# hv_io_connector.net
KiCad netlist of a schematic drawn in Altium Designer
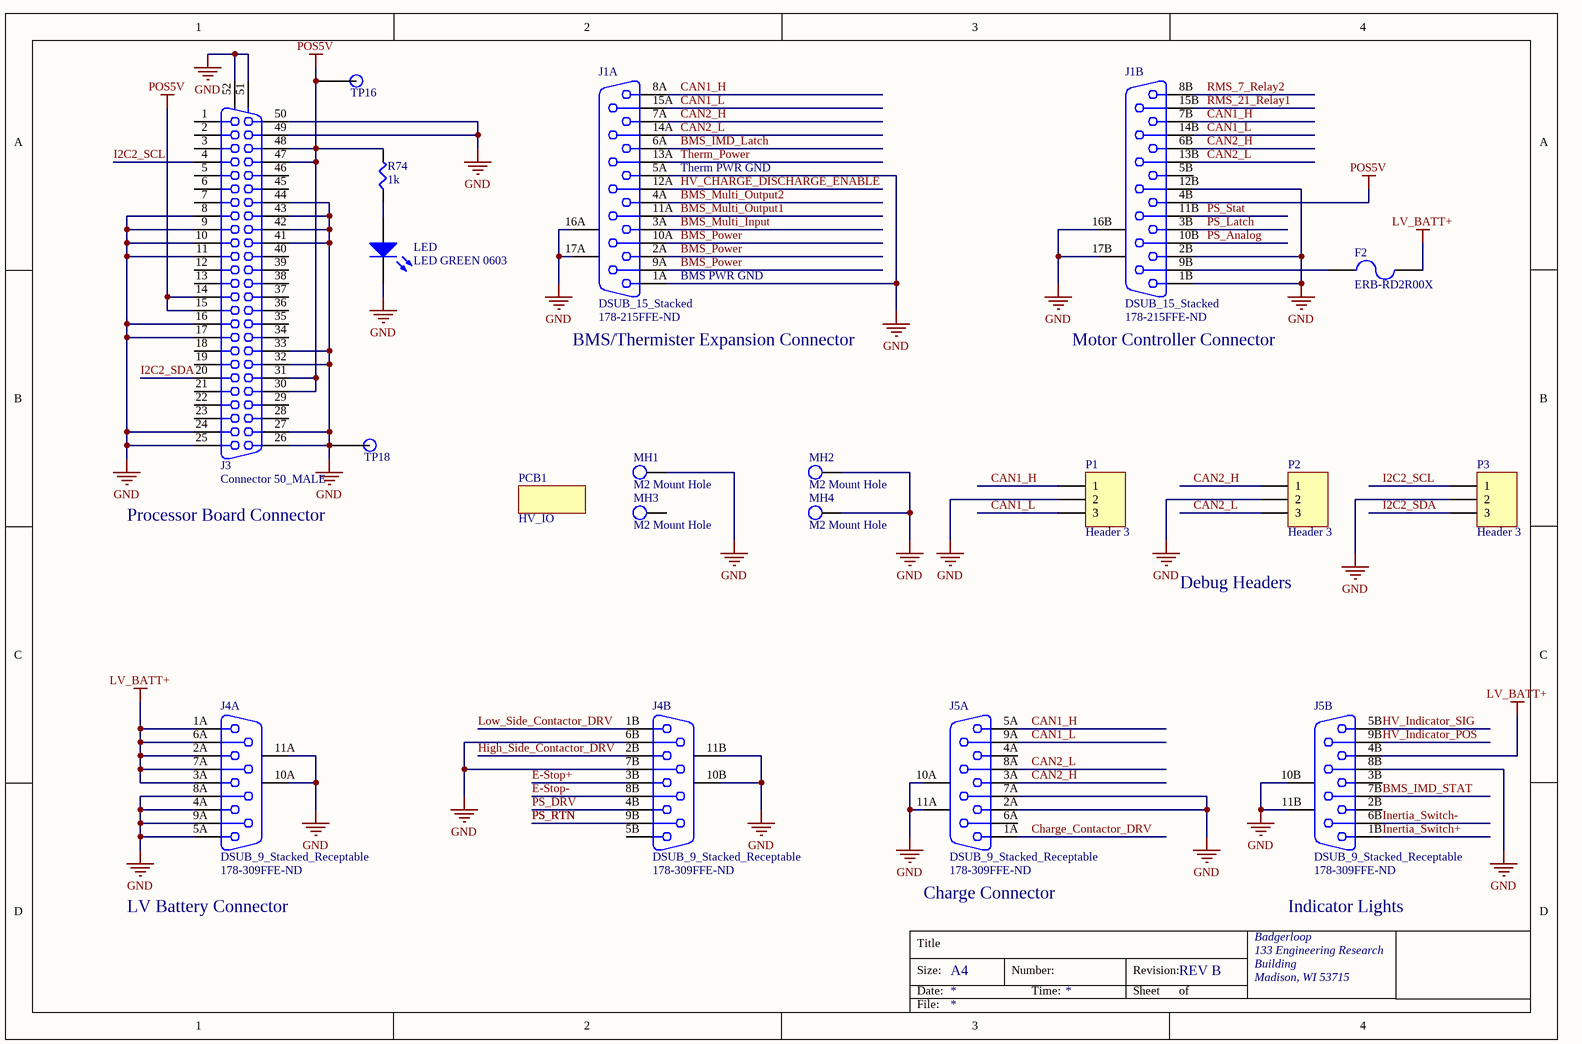
[diagram p0: hv_io_connector.SchDoc]

(export (version "E")
  (design (tool "Eeschema 10.0.6"))
  (components
    (comp (ref "F2")
      (value "ERB-RD2R00X")
      (footprint "SMD-0402-RES")
      (description "FUSE BOARD MOUNT 2A 32VDC 0402")
      (fields (field (name "MANUFACTURER") "Panasonic"))
      (libsource (lib "temp") (part "ERB-RD2R00X"))
    )
    (comp (ref "J1")
      (value "DSUB_15_Stacked")
      (footprint "DSUB_15_Stacked")
      (description "CONN D-SUB RCPT 15POS R/A SLDR")
      (fields
        (field (name "MANUFACTURER") "NorComp")
        (field (name "MANUFACTURER PART NUMBER") "178-015-513R491")
        (field (name "SUPPLIER PART NUMBER 1") "178-215FFE-ND")
      )
      (libsource (lib "temp") (part "DSUB_15_Stacked"))
    )
    (comp (ref "J3")
      (value "Connector 50_MALE")
      (footprint "050DSUB1.27-H96 - Male")
      (description "Receptacle Header Assemby")
      (fields (field (name "MANUFACTURER") "HARTING"))
      (libsource (lib "connector") (part "Connector 50_MALE"))
    )
    (comp (ref "J4")
      (value "DSUB_9_Stacked_Receptable")
      (footprint "DSUB_9_Stacked")
      (description "CONN D-SUB RCPT 9POS R/A SLDR")
      (fields
        (field (name "MANUFACTURER") "NorComp")
        (field (name "MANUFACTURER PART NUMBER") "178-009-513R691")
        (field (name "SUPPLIER PART NUMBER 1") "178-309FFE-ND")
      )
      (libsource (lib "temp") (part "DSUB_9_Stacked_Receptable"))
    )
    (comp (ref "J5")
      (value "DSUB_9_Stacked_Receptable")
      (footprint "DSUB_9_Stacked")
      (description "CONN D-SUB RCPT 9POS R/A SLDR")
      (fields
        (field (name "MANUFACTURER") "NorComp")
        (field (name "MANUFACTURER PART NUMBER") "178-009-513R691")
        (field (name "SUPPLIER PART NUMBER 1") "178-309FFE-ND")
      )
      (libsource (lib "temp") (part "DSUB_9_Stacked_Receptable"))
    )
    (comp (ref "LED")
      (value "LED GREEN 0603")
      (footprint "LED 0603 GREEN")
      (fields (field (name "MANUFACTURER") "Lite-On Inc."))
      (libsource (lib "altium-import") (part "root_3_LED GREEN 0603_"))
    )
    (comp (ref "MH1")
      (value "M2 Mount Hole")
      (footprint "MH")
      (libsource (lib "altium-import") (part "root_0_M2 Mount Hole_"))
    )
    (comp (ref "MH2")
      (value "M2 Mount Hole")
      (footprint "MH")
      (libsource (lib "altium-import") (part "root_0_M2 Mount Hole_"))
    )
    (comp (ref "MH3")
      (value "M2 Mount Hole")
      (footprint "MH")
      (libsource (lib "altium-import") (part "root_0_M2 Mount Hole_"))
    )
    (comp (ref "MH4")
      (value "M2 Mount Hole")
      (footprint "MH")
      (libsource (lib "altium-import") (part "root_0_M2 Mount Hole_"))
    )
    (comp (ref "P1")
      (value "Header 3")
      (footprint "Pin Header 1x3 TH Pitch 2.54mm")
      (description "Header, 3-Pin")
      (fields (field (name "PUBLISHER") "Altium Limited"))
      (libsource (lib "altium-import") (part "root_0_Header 3_"))
    )
    (comp (ref "P2")
      (value "Header 3")
      (footprint "Pin Header 1x3 TH Pitch 2.54mm")
      (description "Header, 3-Pin")
      (fields (field (name "PUBLISHER") "Altium Limited"))
      (libsource (lib "altium-import") (part "root_0_Header 3_"))
    )
    (comp (ref "P3")
      (value "Header 3")
      (footprint "Pin Header 1x3 TH Pitch 2.54mm")
      (description "Header, 3-Pin")
      (fields (field (name "PUBLISHER") "Altium Limited"))
      (libsource (lib "altium-import") (part "root_0_Header 3_"))
    )
    (comp (ref "PCB1") (value "HV_IO") (footprint "PCB") (libsource (lib "temp") (part "PCB")))
    (comp (ref "R74")
      (value "1k")
      (footprint "SMD-0805-RES")
      (description "RES SMD 1K OHM 5% 1/2W 0805")
      (fields
        (field (name "PART NUMBER") "ERJ-P06J102V")
        (field (name "DIGI-KEY PART NUMBER") "P1.0KADCT-ND")
      )
      (libsource (lib "altium-import") (part "root_1_ERJ-P06J102V_"))
    )
    (comp (ref "TP16") (value "TP") (footprint "Test Point") (libsource (lib "misc") (part "TP")))
    (comp (ref "TP18") (value "TP") (footprint "Test Point") (libsource (lib "misc") (part "TP")))
  )
  (nets
    (net (code "1") (name "/BMS_IMD_Latch") (class "Default")
      (node (ref "J1") (pin "6A") (pinfunction "6_6A") (pintype "passive"))
    )
    (net (code "2") (name "/BMS_IMD_STAT") (class "Default")
      (node (ref "J5") (pin "7B") (pinfunction "7_7B") (pintype "passive"))
    )
    (net (code "3") (name "/BMS_Multi_Input") (class "Default")
      (node (ref "J1") (pin "3A") (pinfunction "3_3A") (pintype "passive"))
    )
    (net (code "4") (name "/BMS_Multi_Output1") (class "Default")
      (node (ref "J1") (pin "11A") (pinfunction "11_11A") (pintype "passive"))
    )
    (net (code "5") (name "/BMS_Multi_Output2") (class "Default")
      (node (ref "J1") (pin "4A") (pinfunction "4_4A") (pintype "passive"))
    )
    (net (code "6") (name "/BMS_Power") (class "Default")
      (node (ref "J1") (pin "10A") (pinfunction "10_10A") (pintype "passive"))
      (node (ref "J1") (pin "2A") (pinfunction "2_2A") (pintype "passive"))
      (node (ref "J1") (pin "9A") (pinfunction "9_9A") (pintype "passive"))
    )
    (net (code "7") (name "/CAN1_H") (class "Default")
      (node (ref "J1") (pin "7B") (pinfunction "7_7B") (pintype "passive"))
      (node (ref "J1") (pin "8A") (pinfunction "8_8A") (pintype "passive"))
      (node (ref "J5") (pin "5A") (pinfunction "5_5A") (pintype "passive"))
      (node (ref "P1") (pin "1") (pinfunction "1_1") (pintype "passive"))
    )
    (net (code "8") (name "/CAN1_L") (class "Default")
      (node (ref "J1") (pin "14B") (pinfunction "14_14B") (pintype "passive"))
      (node (ref "J1") (pin "15A") (pinfunction "15_15A") (pintype "passive"))
      (node (ref "J5") (pin "9A") (pinfunction "9_9A") (pintype "passive"))
      (node (ref "P1") (pin "3") (pinfunction "3_3") (pintype "passive"))
    )
    (net (code "9") (name "/CAN2_H") (class "Default")
      (node (ref "J1") (pin "6B") (pinfunction "6_6B") (pintype "passive"))
      (node (ref "J1") (pin "7A") (pinfunction "7_7A") (pintype "passive"))
      (node (ref "J5") (pin "3A") (pinfunction "3_3A") (pintype "passive"))
      (node (ref "P2") (pin "1") (pinfunction "1_1") (pintype "passive"))
    )
    (net (code "10") (name "/CAN2_L") (class "Default")
      (node (ref "J1") (pin "13B") (pinfunction "13_13B") (pintype "passive"))
      (node (ref "J1") (pin "14A") (pinfunction "14_14A") (pintype "passive"))
      (node (ref "J5") (pin "8A") (pinfunction "8_8A") (pintype "passive"))
      (node (ref "P2") (pin "3") (pinfunction "3_3") (pintype "passive"))
    )
    (net (code "11") (name "/Charge_Contactor_DRV") (class "Default")
      (node (ref "J5") (pin "1A") (pinfunction "1_1A") (pintype "passive"))
    )
    (net (code "12") (name "/E-Stop+") (class "Default")
      (node (ref "J4") (pin "3B") (pinfunction "3_3B") (pintype "passive"))
    )
    (net (code "13") (name "/E-Stop-") (class "Default")
      (node (ref "J4") (pin "8B") (pinfunction "8_8B") (pintype "passive"))
    )
    (net (code "14") (name "/HV_CHARGE_DISCHARGE_ENABLE") (class "Default")
      (node (ref "J1") (pin "12A") (pinfunction "12_12A") (pintype "passive"))
    )
    (net (code "15") (name "/HV_Indicator_POS") (class "Default")
      (node (ref "J5") (pin "9B") (pinfunction "9_9B") (pintype "passive"))
    )
    (net (code "16") (name "/HV_Indicator_SIG") (class "Default")
      (node (ref "J5") (pin "5B") (pinfunction "5_5B") (pintype "passive"))
    )
    (net (code "17") (name "/High_Side_Contactor_DRV") (class "Default")
      (node (ref "J4") (pin "2B") (pinfunction "2_2B") (pintype "passive"))
    )
    (net (code "18") (name "/I2C2_SCL") (class "Default")
      (node (ref "J3") (pin "4") (pinfunction "4_4") (pintype "passive"))
      (node (ref "P3") (pin "1") (pinfunction "1_1") (pintype "passive"))
    )
    (net (code "19") (name "/I2C2_SDA") (class "Default")
      (node (ref "J3") (pin "20") (pinfunction "20_20") (pintype "passive"))
      (node (ref "P3") (pin "3") (pinfunction "3_3") (pintype "passive"))
    )
    (net (code "20") (name "/Inertia_Switch+") (class "Default")
      (node (ref "J5") (pin "1B") (pinfunction "1_1B") (pintype "passive"))
    )
    (net (code "21") (name "/Inertia_Switch-") (class "Default")
      (node (ref "J5") (pin "6B") (pinfunction "6_6B") (pintype "passive"))
    )
    (net (code "22") (name "/Low_Side_Contactor_DRV") (class "Default")
      (node (ref "J4") (pin "1B") (pinfunction "1_1B") (pintype "passive"))
    )
    (net (code "23") (name "/PS_Analog") (class "Default")
      (node (ref "J1") (pin "10B") (pinfunction "10_10B") (pintype "passive"))
    )
    (net (code "24") (name "/PS_DRV") (class "Default")
      (node (ref "J4") (pin "4B") (pinfunction "4_4B") (pintype "passive"))
    )
    (net (code "25") (name "/PS_Latch") (class "Default")
      (node (ref "J1") (pin "3B") (pinfunction "3_3B") (pintype "passive"))
    )
    (net (code "26") (name "/PS_RTN") (class "Default")
      (node (ref "J4") (pin "9B") (pinfunction "9_9B") (pintype "passive"))
    )
    (net (code "27") (name "/PS_Stat") (class "Default")
      (node (ref "J1") (pin "11B") (pinfunction "11_11B") (pintype "passive"))
    )
    (net (code "28") (name "/RMS_7_Relay2") (class "Default")
      (node (ref "J1") (pin "8B") (pinfunction "8_8B") (pintype "passive"))
    )
    (net (code "29") (name "/RMS_21_Relay1") (class "Default")
      (node (ref "J1") (pin "15B") (pinfunction "15_15B") (pintype "passive"))
    )
    (net (code "30") (name "/Therm_Power") (class "Default")
      (node (ref "J1") (pin "13A") (pinfunction "13_13A") (pintype "passive"))
    )
    (net (code "31") (name "GND") (class "Default")
      (node (ref "J1") (pin "12B") (pinfunction "12_12B") (pintype "passive"))
      (node (ref "J1") (pin "16A") (pinfunction "MH1_16A") (pintype "passive"))
      (node (ref "J1") (pin "16B") (pinfunction "MH1_16B") (pintype "passive"))
      (node (ref "J1") (pin "17A") (pinfunction "MH2_17A") (pintype "passive"))
      (node (ref "J1") (pin "17B") (pinfunction "MH2_17B") (pintype "passive"))
      (node (ref "J1") (pin "1A") (pinfunction "1_1A") (pintype "passive"))
      (node (ref "J1") (pin "1B") (pinfunction "1_1B") (pintype "passive"))
      (node (ref "J1") (pin "2B") (pinfunction "2_2B") (pintype "passive"))
      (node (ref "J1") (pin "5A") (pinfunction "5_5A") (pintype "passive"))
      (node (ref "J3") (pin "10") (pinfunction "10_10") (pintype "passive"))
      (node (ref "J3") (pin "11") (pinfunction "11_11") (pintype "passive"))
      (node (ref "J3") (pin "16") (pinfunction "16_16") (pintype "passive"))
      (node (ref "J3") (pin "17") (pinfunction "17_17") (pintype "passive"))
      (node (ref "J3") (pin "24") (pinfunction "24_24") (pintype "passive"))
      (node (ref "J3") (pin "25") (pinfunction "25_25") (pintype "passive"))
      (node (ref "J3") (pin "26") (pinfunction "26_26") (pintype "passive"))
      (node (ref "J3") (pin "27") (pinfunction "27_27") (pintype "passive"))
      (node (ref "J3") (pin "32") (pinfunction "32_32") (pintype "passive"))
      (node (ref "J3") (pin "33") (pinfunction "33_33") (pintype "passive"))
      (node (ref "J3") (pin "41") (pinfunction "41_41") (pintype "passive"))
      (node (ref "J3") (pin "42") (pinfunction "42_42") (pintype "passive"))
      (node (ref "J3") (pin "43") (pinfunction "43_43") (pintype "passive"))
      (node (ref "J3") (pin "44") (pinfunction "44_44") (pintype "passive"))
      (node (ref "J3") (pin "49") (pinfunction "49_49") (pintype "passive"))
      (node (ref "J3") (pin "50") (pinfunction "50_50") (pintype "passive"))
      (node (ref "J3") (pin "51") (pinfunction "51_51") (pintype "passive"))
      (node (ref "J3") (pin "52") (pinfunction "52_52") (pintype "passive"))
      (node (ref "J3") (pin "8") (pinfunction "8_8") (pintype "passive"))
      (node (ref "J3") (pin "9") (pinfunction "9_9") (pintype "passive"))
      (node (ref "J4") (pin "10A") (pinfunction "MH1_10A") (pintype "passive"))
      (node (ref "J4") (pin "10B") (pinfunction "MH1_10B") (pintype "passive"))
      (node (ref "J4") (pin "11A") (pinfunction "MH2_11A") (pintype "passive"))
      (node (ref "J4") (pin "11B") (pinfunction "MH2_11B") (pintype "passive"))
      (node (ref "J4") (pin "4A") (pinfunction "4_4A") (pintype "passive"))
      (node (ref "J4") (pin "5A") (pinfunction "5_5A") (pintype "passive"))
      (node (ref "J4") (pin "6B") (pinfunction "6_6B") (pintype "passive"))
      (node (ref "J4") (pin "7B") (pinfunction "7_7B") (pintype "passive"))
      (node (ref "J4") (pin "8A") (pinfunction "8_8A") (pintype "passive"))
      (node (ref "J4") (pin "9A") (pinfunction "9_9A") (pintype "passive"))
      (node (ref "J5") (pin "10A") (pinfunction "MH1_10A") (pintype "passive"))
      (node (ref "J5") (pin "10B") (pinfunction "MH1_10B") (pintype "passive"))
      (node (ref "J5") (pin "11A") (pinfunction "MH2_11A") (pintype "passive"))
      (node (ref "J5") (pin "11B") (pinfunction "MH2_11B") (pintype "passive"))
      (node (ref "J5") (pin "2A") (pinfunction "2_2A") (pintype "passive"))
      (node (ref "J5") (pin "7A") (pinfunction "7_7A") (pintype "passive"))
      (node (ref "J5") (pin "8B") (pinfunction "8_8B") (pintype "passive"))
      (node (ref "LED") (pin "2") (pinfunction "K_2") (pintype "passive"))
      (node (ref "MH1") (pin "1") (pinfunction "1_1") (pintype "passive"))
      (node (ref "MH2") (pin "1") (pinfunction "1_1") (pintype "passive"))
      (node (ref "MH4") (pin "1") (pinfunction "1_1") (pintype "passive"))
      (node (ref "P1") (pin "2") (pinfunction "2_2") (pintype "passive"))
      (node (ref "P2") (pin "2") (pinfunction "2_2") (pintype "passive"))
      (node (ref "P3") (pin "2") (pinfunction "2_2") (pintype "passive"))
      (node (ref "TP18") (pin "1") (pinfunction "1_1") (pintype "passive"))
    )
    (net (code "32") (name "LV_BATT+") (class "Default")
      (node (ref "F2") (pin "2") (pinfunction "2_2") (pintype "passive"))
      (node (ref "J4") (pin "1A") (pinfunction "1_1A") (pintype "passive"))
      (node (ref "J4") (pin "2A") (pinfunction "2_2A") (pintype "passive"))
      (node (ref "J4") (pin "3A") (pinfunction "3_3A") (pintype "passive"))
      (node (ref "J4") (pin "6A") (pinfunction "6_6A") (pintype "passive"))
      (node (ref "J4") (pin "7A") (pinfunction "7_7A") (pintype "passive"))
      (node (ref "J5") (pin "4B") (pinfunction "4_4B") (pintype "passive"))
    )
    (net (code "33") (name "Net-(J1B-9)") (class "Default")
      (node (ref "F2") (pin "1") (pinfunction "1_1") (pintype "passive"))
      (node (ref "J1") (pin "9B") (pinfunction "9_9B") (pintype "passive"))
    )
    (net (code "34") (name "Net-(LED-A)") (class "Default")
      (node (ref "LED") (pin "1") (pinfunction "A_1") (pintype "passive"))
      (node (ref "R74") (pin "1") (pinfunction "1_1") (pintype "passive"))
    )
    (net (code "35") (name "POS5V") (class "Default")
      (node (ref "J1") (pin "4B") (pinfunction "4_4B") (pintype "passive"))
      (node (ref "J3") (pin "14") (pinfunction "14_14") (pintype "passive"))
      (node (ref "J3") (pin "15") (pinfunction "15_15") (pintype "passive"))
      (node (ref "J3") (pin "30") (pinfunction "30_30") (pintype "passive"))
      (node (ref "J3") (pin "31") (pinfunction "31_31") (pintype "passive"))
      (node (ref "J3") (pin "47") (pinfunction "47_47") (pintype "passive"))
      (node (ref "J3") (pin "48") (pinfunction "48_48") (pintype "passive"))
      (node (ref "R74") (pin "2") (pinfunction "2_2") (pintype "passive"))
      (node (ref "TP16") (pin "1") (pinfunction "1_1") (pintype "passive"))
    )
    (net (code "36") (name "unconnected-(J1B-5-Pad5B)") (class "Default")
      (node (ref "J1") (pin "5B") (pinfunction "5_5B") (pintype "passive"))
    )
    (net (code "37") (name "unconnected-(J3-Pad1)") (class "Default")
      (node (ref "J3") (pin "1") (pinfunction "1_1") (pintype "passive"))
    )
    (net (code "38") (name "unconnected-(J3-Pad2)") (class "Default")
      (node (ref "J3") (pin "2") (pinfunction "2_2") (pintype "passive"))
    )
    (net (code "39") (name "unconnected-(J3-Pad3)") (class "Default")
      (node (ref "J3") (pin "3") (pinfunction "3_3") (pintype "passive"))
    )
    (net (code "40") (name "unconnected-(J3-Pad5)") (class "Default")
      (node (ref "J3") (pin "5") (pinfunction "5_5") (pintype "passive"))
    )
    (net (code "41") (name "unconnected-(J3-Pad6)") (class "Default")
      (node (ref "J3") (pin "6") (pinfunction "6_6") (pintype "passive"))
    )
    (net (code "42") (name "unconnected-(J3-Pad7)") (class "Default")
      (node (ref "J3") (pin "7") (pinfunction "7_7") (pintype "passive"))
    )
    (net (code "43") (name "unconnected-(J3-Pad12)") (class "Default")
      (node (ref "J3") (pin "12") (pinfunction "12_12") (pintype "passive"))
    )
    (net (code "44") (name "unconnected-(J3-Pad13)") (class "Default")
      (node (ref "J3") (pin "13") (pinfunction "13_13") (pintype "passive"))
    )
    (net (code "45") (name "unconnected-(J3-Pad18)") (class "Default")
      (node (ref "J3") (pin "18") (pinfunction "18_18") (pintype "passive"))
    )
    (net (code "46") (name "unconnected-(J3-Pad19)") (class "Default")
      (node (ref "J3") (pin "19") (pinfunction "19_19") (pintype "passive"))
    )
    (net (code "47") (name "unconnected-(J3-Pad21)") (class "Default")
      (node (ref "J3") (pin "21") (pinfunction "21_21") (pintype "passive"))
    )
    (net (code "48") (name "unconnected-(J3-Pad22)") (class "Default")
      (node (ref "J3") (pin "22") (pinfunction "22_22") (pintype "passive"))
    )
    (net (code "49") (name "unconnected-(J3-Pad23)") (class "Default")
      (node (ref "J3") (pin "23") (pinfunction "23_23") (pintype "passive"))
    )
    (net (code "50") (name "unconnected-(J3-Pad28)") (class "Default")
      (node (ref "J3") (pin "28") (pinfunction "28_28") (pintype "passive"))
    )
    (net (code "51") (name "unconnected-(J3-Pad29)") (class "Default")
      (node (ref "J3") (pin "29") (pinfunction "29_29") (pintype "passive"))
    )
    (net (code "52") (name "unconnected-(J3-Pad34)") (class "Default")
      (node (ref "J3") (pin "34") (pinfunction "34_34") (pintype "passive"))
    )
    (net (code "53") (name "unconnected-(J3-Pad35)") (class "Default")
      (node (ref "J3") (pin "35") (pinfunction "35_35") (pintype "passive"))
    )
    (net (code "54") (name "unconnected-(J3-Pad36)") (class "Default")
      (node (ref "J3") (pin "36") (pinfunction "36_36") (pintype "passive"))
    )
    (net (code "55") (name "unconnected-(J3-Pad37)") (class "Default")
      (node (ref "J3") (pin "37") (pinfunction "37_37") (pintype "passive"))
    )
    (net (code "56") (name "unconnected-(J3-Pad38)") (class "Default")
      (node (ref "J3") (pin "38") (pinfunction "38_38") (pintype "passive"))
    )
    (net (code "57") (name "unconnected-(J3-Pad39)") (class "Default")
      (node (ref "J3") (pin "39") (pinfunction "39_39") (pintype "passive"))
    )
    (net (code "58") (name "unconnected-(J3-Pad40)") (class "Default")
      (node (ref "J3") (pin "40") (pinfunction "40_40") (pintype "passive"))
    )
    (net (code "59") (name "unconnected-(J3-Pad45)") (class "Default")
      (node (ref "J3") (pin "45") (pinfunction "45_45") (pintype "passive"))
    )
    (net (code "60") (name "unconnected-(J3-Pad46)") (class "Default")
      (node (ref "J3") (pin "46") (pinfunction "46_46") (pintype "passive"))
    )
    (net (code "61") (name "unconnected-(J4B-5-Pad5B)") (class "Default")
      (node (ref "J4") (pin "5B") (pinfunction "5_5B") (pintype "passive"))
    )
    (net (code "62") (name "unconnected-(J5A-4-Pad4A)") (class "Default")
      (node (ref "J5") (pin "4A") (pinfunction "4_4A") (pintype "passive"))
    )
    (net (code "63") (name "unconnected-(J5A-6-Pad6A)") (class "Default")
      (node (ref "J5") (pin "6A") (pinfunction "6_6A") (pintype "passive"))
    )
    (net (code "64") (name "unconnected-(J5B-2-Pad2B)") (class "Default")
      (node (ref "J5") (pin "2B") (pinfunction "2_2B") (pintype "passive"))
    )
    (net (code "65") (name "unconnected-(J5B-3-Pad3B)") (class "Default")
      (node (ref "J5") (pin "3B") (pinfunction "3_3B") (pintype "passive"))
    )
    (net (code "66") (name "unconnected-(MH3-Pad1)") (class "Default")
      (node (ref "MH3") (pin "1") (pinfunction "1_1") (pintype "passive"))
    )
  )
)
